# DIOT_SMA16.net
KiCad netlist of a schematic drawn in Altium Designer
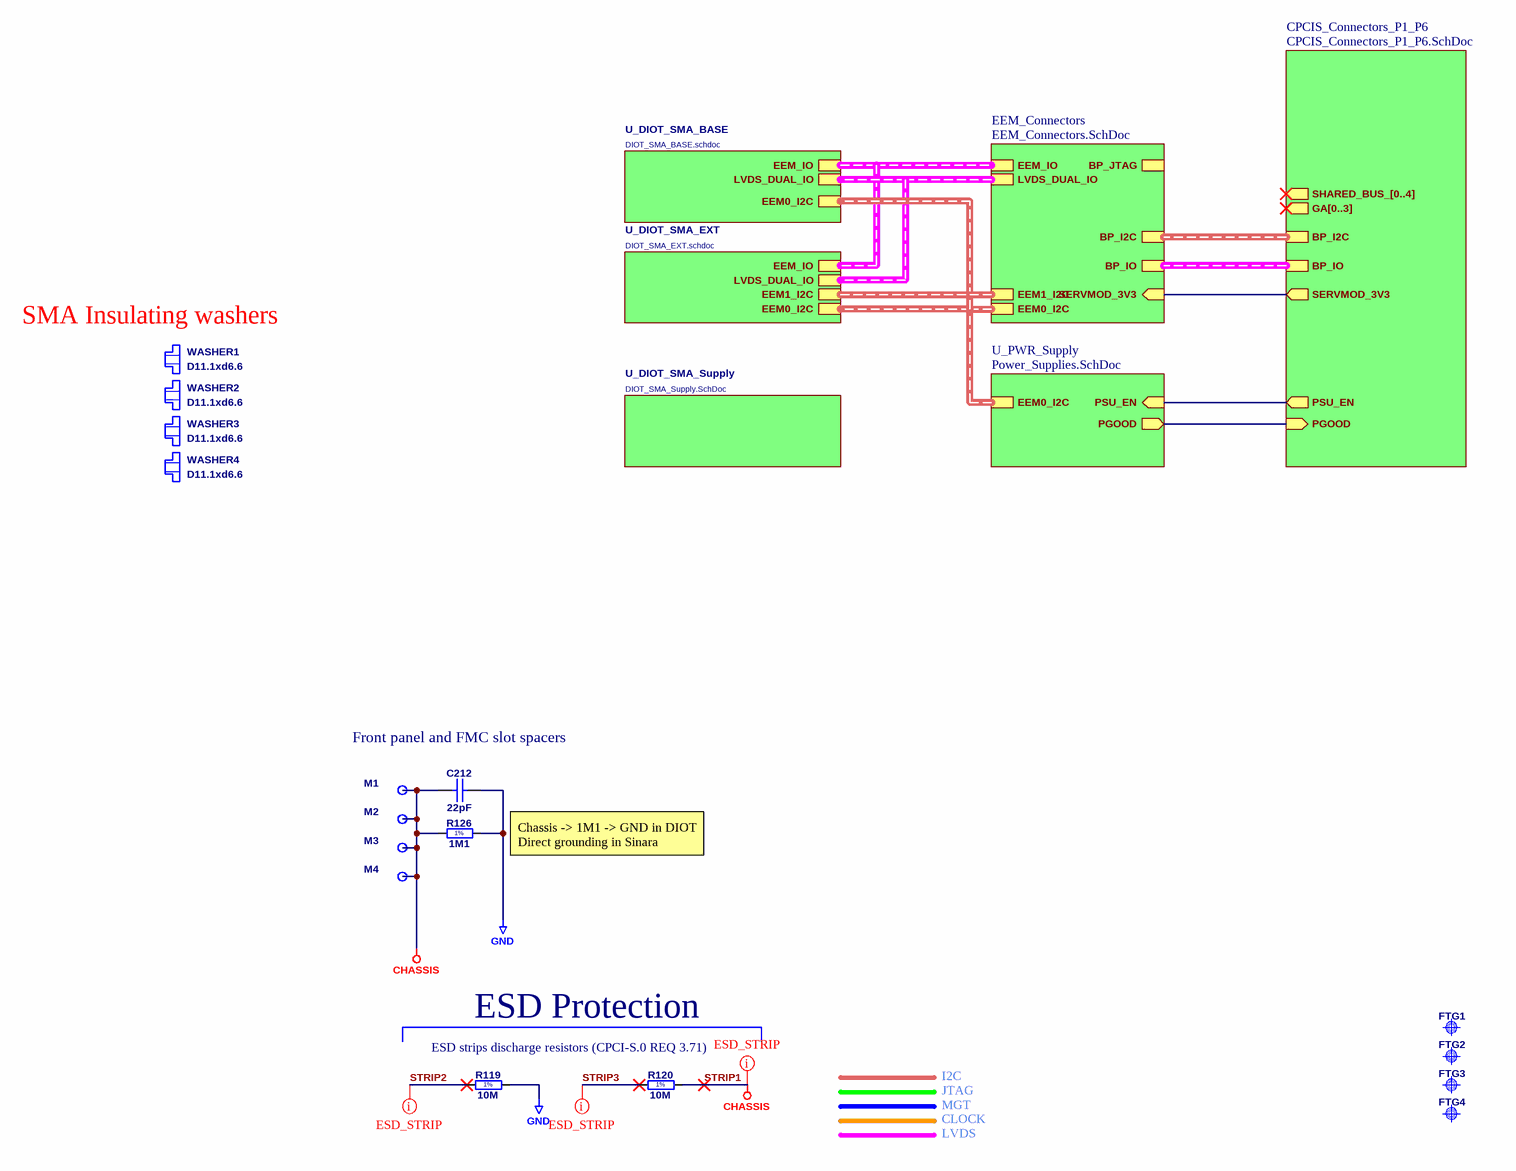
[diagram p0: DIOT_SMA16.SchDoc]

(export (version "E")
  (design (tool "Eeschema 10.0.6"))
  (components
    (comp (ref "C212")
      (value "22pF")
      (footprint "CAPC1005X55N")
      (description "Non-polarised capacitor")
      (fields
        (field (name "PART NUMBER") "CC0402_22PF_50V_5%_C0G")
        (field (name "VOLTAGE") "50V")
        (field (name "AUTHOR") "CERN DEM JLC")
      )
      (libsource (lib "Capacitors") (part "Capacitor - non polarized"))
    )
    (comp (ref "FTG1")
      (value "Use only in PCB")
      (footprint "FIDUCIAL_TOP_C100-200")
      (description "Fiducial Target")
      (fields (field (name "PART NUMBER") "FIDUCIAL_TARGET_C100-200") (field (name "AUTHOR") "CERN DEM JLC"))
      (libsource (lib "Eletro-mechanical") (part "Fiducial Target"))
    )
    (comp (ref "FTG2")
      (value "Use only in PCB")
      (footprint "FIDUCIAL_TOP_S100-200")
      (description "Fiducial Target")
      (fields (field (name "PART NUMBER") "FIDUCIAL_TARGET_S100-200") (field (name "AUTHOR") "CERN DEM JLC"))
      (libsource (lib "Eletro-mechanical") (part "Fiducial Target"))
    )
    (comp (ref "FTG3")
      (value "Use only in PCB")
      (footprint "FIDUCIAL_TOP_S100-200")
      (description "Fiducial Target")
      (fields (field (name "PART NUMBER") "FIDUCIAL_TARGET_S100-200") (field (name "AUTHOR") "CERN DEM JLC"))
      (libsource (lib "Eletro-mechanical") (part "Fiducial Target"))
    )
    (comp (ref "FTG4")
      (value "Use only in PCB")
      (footprint "FIDUCIAL_TOP_S100-200")
      (description "Fiducial Target")
      (fields (field (name "PART NUMBER") "FIDUCIAL_TARGET_S100-200") (field (name "AUTHOR") "CERN DEM JLC"))
      (libsource (lib "Eletro-mechanical") (part "Fiducial Target"))
    )
    (comp (ref "M1")
      (value "Plated Hole")
      (footprint "MTG300_600")
      (description "Single Terminal Socket")
      (fields (field (name "PART NUMBER") "PLATED_HOLE3.0_PAD6.0") (field (name "AUTHOR") "CERN DEM JLC"))
      (libsource (lib "Eletro-mechanical") (part "Single Terminal Socket"))
    )
    (comp (ref "M2")
      (value "Plated Hole")
      (footprint "MTG300_600")
      (description "Single Terminal Socket")
      (fields (field (name "PART NUMBER") "PLATED_HOLE3.0_PAD6.0") (field (name "AUTHOR") "CERN DEM JLC"))
      (libsource (lib "Eletro-mechanical") (part "Single Terminal Socket"))
    )
    (comp (ref "M3")
      (value "Plated Hole")
      (footprint "MTG300_600")
      (description "Single Terminal Socket")
      (fields (field (name "PART NUMBER") "PLATED_HOLE3.0_PAD6.0") (field (name "AUTHOR") "CERN DEM JLC"))
      (libsource (lib "Eletro-mechanical") (part "Single Terminal Socket"))
    )
    (comp (ref "M4")
      (value "Plated Hole")
      (footprint "MTG300_600")
      (description "Single Terminal Socket")
      (fields (field (name "PART NUMBER") "PLATED_HOLE3.0_PAD6.0") (field (name "AUTHOR") "CERN DEM JLC"))
      (libsource (lib "Eletro-mechanical") (part "Single Terminal Socket"))
    )
    (comp (ref "R119")
      (value "10M")
      (footprint "RESC2113X55N")
      (description "Resistor - 1%")
      (fields
        (field (name "PART NUMBER") "R0805_10M_1%_0.125W_100PPM_VISHAY_CRCW e3")
        (field (name "POWER") "0.125W")
        (field (name "AUTHOR") "CERN DEM BC")
      )
      (libsource (lib "Resistors") (part "Resistor - 1%"))
    )
    (comp (ref "R120")
      (value "10M")
      (footprint "RESC2113X55N")
      (description "Resistor - 1%")
      (fields
        (field (name "PART NUMBER") "R0805_10M_1%_0.125W_100PPM_VISHAY_CRCW e3")
        (field (name "POWER") "0.125W")
        (field (name "AUTHOR") "CERN DEM BC")
      )
      (libsource (lib "Resistors") (part "Resistor - 1%"))
    )
    (comp (ref "R126")
      (value "1M1")
      (footprint "RESC2012X60N")
      (description "Resistor - 1%")
      (fields
        (field (name "PART NUMBER") "R0805_1M1_1%_0.125W_100PPM")
        (field (name "MANUFACTURER") "GENERIC")
        (field (name "AUTHOR") "CERN DEM JLC")
      )
      (libsource (lib "Resistors") (part "Resistor - 1%"))
    )
    (comp (ref "WASHER1")
      (value "D11.1xd6.6")
      (footprint "Keystone_7687")
      (description "SMA_Shoulder Washer")
      (fields (field (name "PART NUMBER") "Custom 3D") (field (name "AUTHOR") "GK"))
      (libsource (lib "LIBRARY_SCH") (part "Keystone_7687"))
    )
    (comp (ref "WASHER2")
      (value "D11.1xd6.6")
      (footprint "Keystone_7687")
      (description "SMA_Shoulder Washer")
      (fields (field (name "PART NUMBER") "Custom 3D") (field (name "AUTHOR") "GK"))
      (libsource (lib "LIBRARY_SCH") (part "Keystone_7687"))
    )
    (comp (ref "WASHER3")
      (value "D11.1xd6.6")
      (footprint "Keystone_7687")
      (description "SMA_Shoulder Washer")
      (fields (field (name "PART NUMBER") "Custom 3D") (field (name "AUTHOR") "GK"))
      (libsource (lib "LIBRARY_SCH") (part "Keystone_7687"))
    )
    (comp (ref "WASHER4")
      (value "D11.1xd6.6")
      (footprint "Keystone_7687")
      (description "SMA_Shoulder Washer")
      (fields (field (name "PART NUMBER") "Custom 3D") (field (name "AUTHOR") "GK"))
      (libsource (lib "LIBRARY_SCH") (part "Keystone_7687"))
    )
  )
  (nets
    (net (code "14") (name "/STRIP2") (class "Default")
      (node (ref "R119") (pin "1") (pinfunction "1_1") (pintype "passive+no_connect"))
    )
    (net (code "15") (name "/STRIP3") (class "Default")
      (node (ref "R120") (pin "1") (pinfunction "1_1") (pintype "passive+no_connect"))
    )
    (net (code "16") (name "CHASSIS") (class "Default")
      (node (ref "C212") (pin "1") (pinfunction "1_1") (pintype "passive"))
      (node (ref "M1") (pin "1") (pinfunction "1_1") (pintype "bidirectional"))
      (node (ref "M2") (pin "1") (pinfunction "1_1") (pintype "bidirectional"))
      (node (ref "M3") (pin "1") (pinfunction "1_1") (pintype "bidirectional"))
      (node (ref "M4") (pin "1") (pinfunction "1_1") (pintype "bidirectional"))
      (node (ref "R120") (pin "2") (pinfunction "2_2") (pintype "passive"))
      (node (ref "R126") (pin "1") (pinfunction "1_1") (pintype "passive"))
    )
    (net (code "17") (name "GND") (class "Default")
      (node (ref "C212") (pin "2") (pinfunction "2_2") (pintype "passive"))
      (node (ref "R119") (pin "2") (pinfunction "2_2") (pintype "passive"))
      (node (ref "R126") (pin "2") (pinfunction "2_2") (pintype "passive"))
    )
  )
)
